# MainBorad.net
KiCad netlist of a schematic drawn in Altium Designer
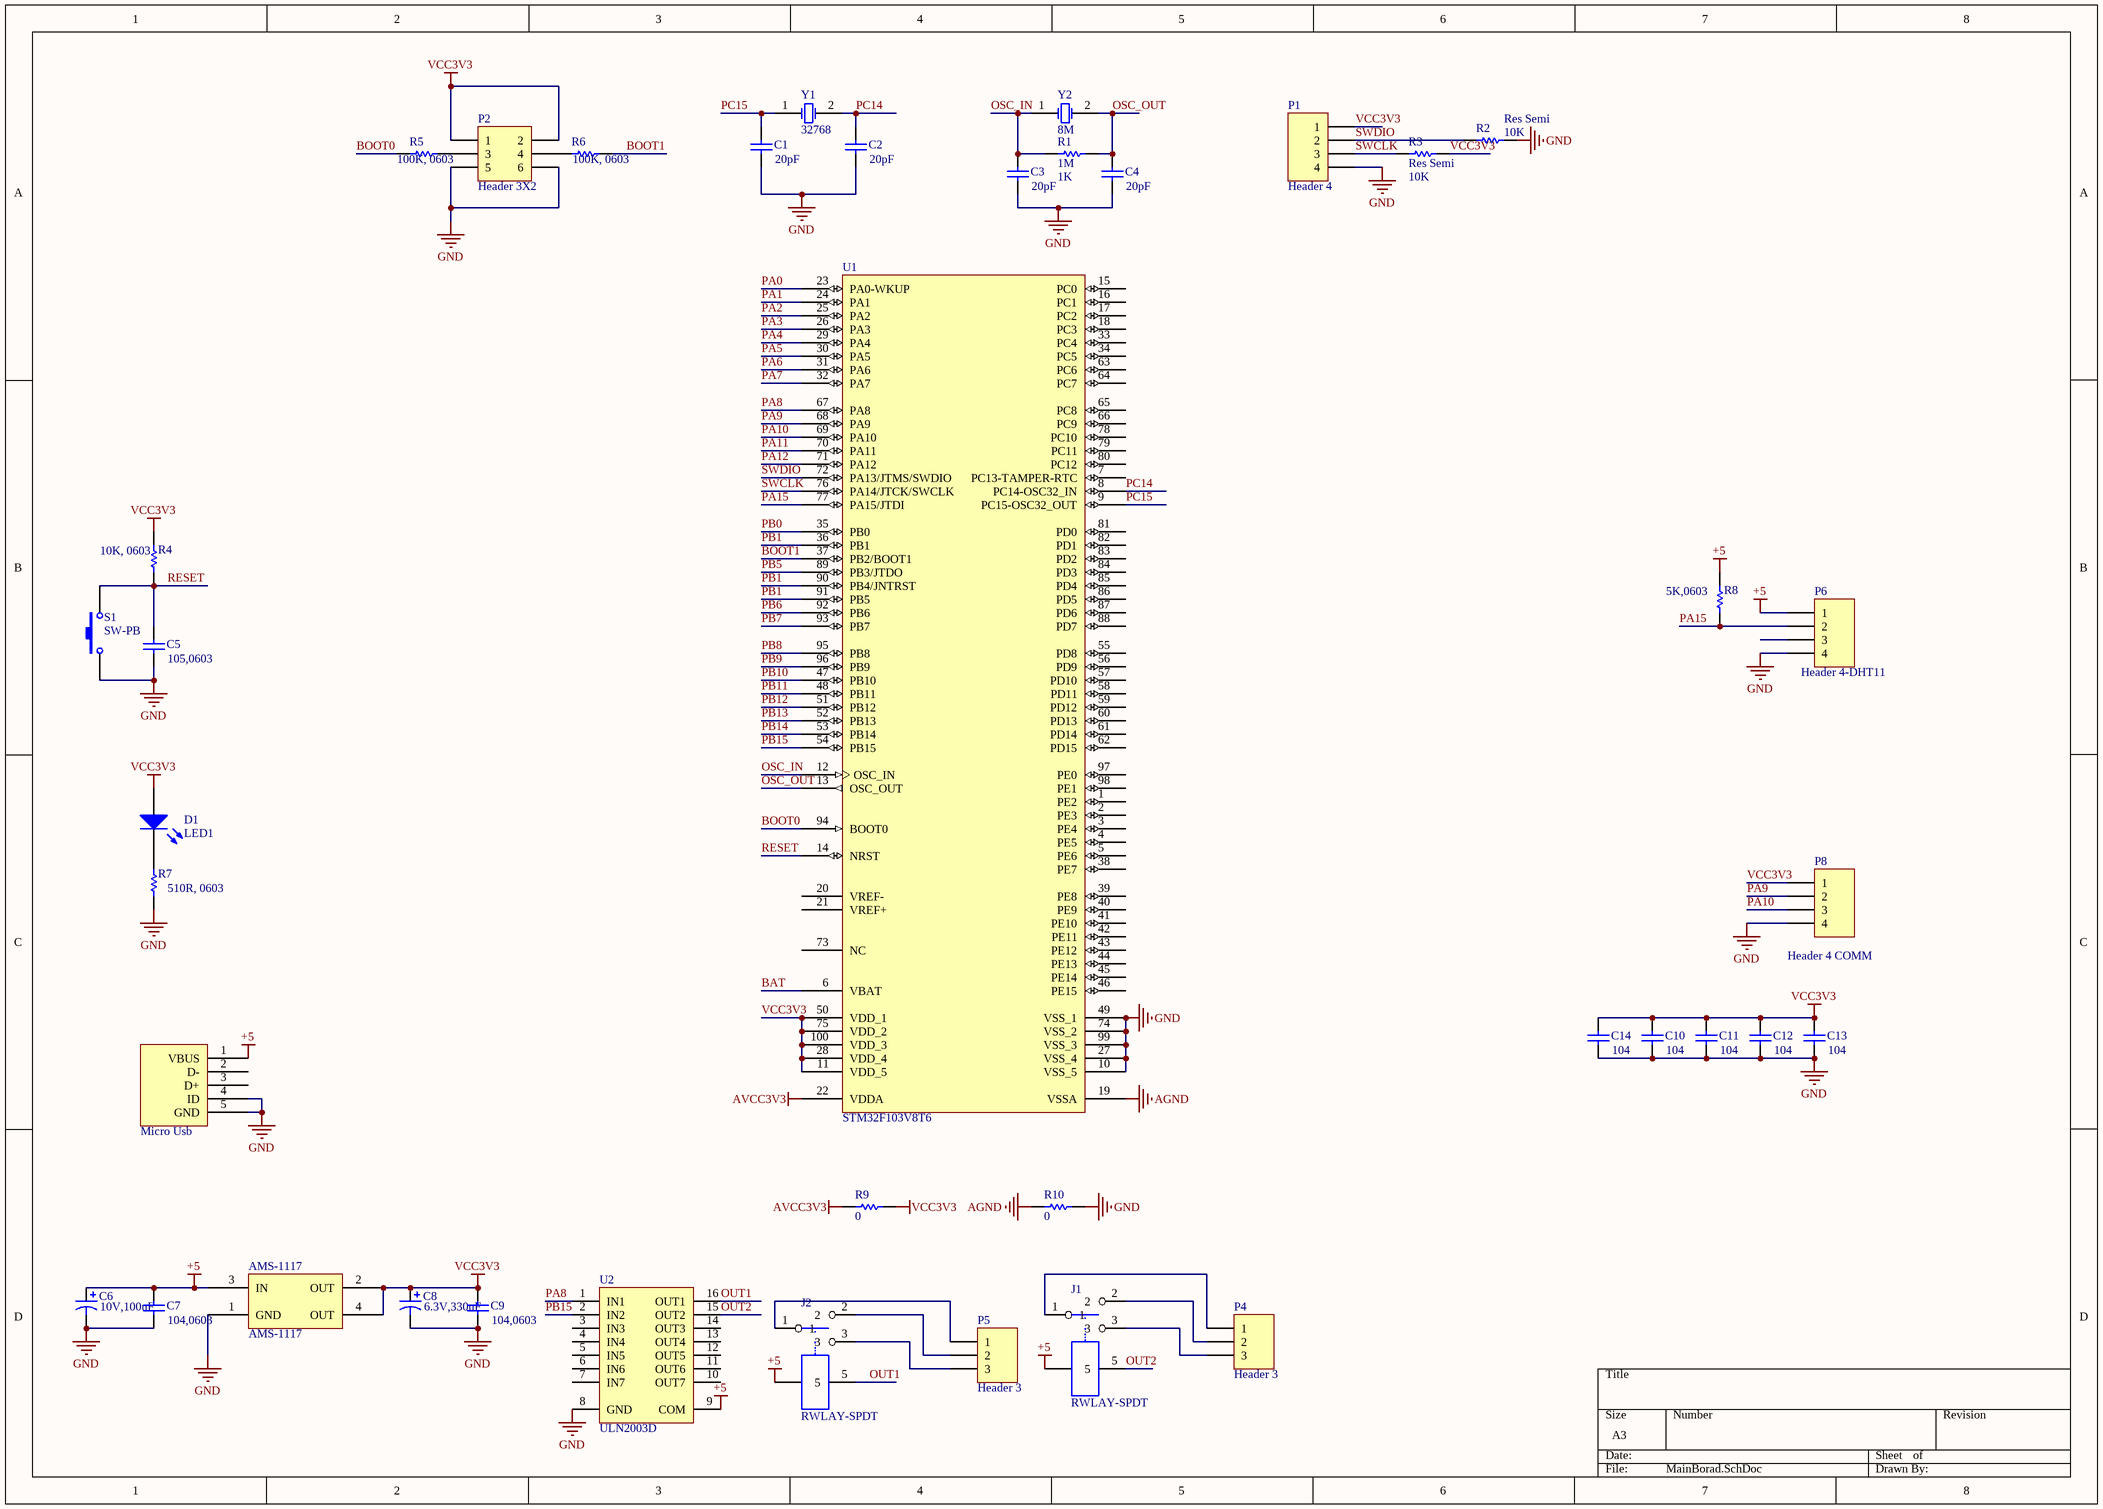
[diagram p0: MainBorad.SchDoc]

(export (version "E")
  (design (tool "Eeschema 10.0.6"))
  (components
    (comp (ref "AMS-1117")
      (value "AMS-1117")
      (footprint "SOT223")
      (libsource (lib "ams1117") (part "AMS-1117"))
    )
    (comp (ref "C1")
      (value "20pF")
      (footprint "0805C")
      (description "Capacitor (Semiconductor SIM Model)")
      (fields (field (name "Comment") "Cap Semi") (field (name "PUBLISHER") "Altium Limited"))
      (libsource (lib "Miscellaneous Devices") (part "Cap Semi"))
    )
    (comp (ref "C2")
      (value "20pF")
      (footprint "0805C")
      (description "Capacitor (Semiconductor SIM Model)")
      (fields (field (name "Comment") "Cap Semi") (field (name "PUBLISHER") "Altium Limited"))
      (libsource (lib "Miscellaneous Devices") (part "Cap Semi"))
    )
    (comp (ref "C3")
      (value "20pF")
      (footprint "0805C")
      (description "Capacitor (Semiconductor SIM Model)")
      (fields (field (name "Comment") "Cap Semi") (field (name "PUBLISHER") "Altium Limited"))
      (libsource (lib "Miscellaneous Devices") (part "Cap Semi"))
    )
    (comp (ref "C4")
      (value "20pF")
      (footprint "0805C")
      (description "Capacitor (Semiconductor SIM Model)")
      (fields (field (name "Comment") "Cap Semi") (field (name "PUBLISHER") "Altium Limited"))
      (libsource (lib "Miscellaneous Devices") (part "Cap Semi"))
    )
    (comp (ref "C5")
      (value "105,0603")
      (footprint "0805C")
      (description "Capacitor (Semiconductor SIM Model)")
      (fields (field (name "Comment") "Cap Semi") (field (name "PUBLISHER") "Altium Limited"))
      (libsource (lib "Miscellaneous Devices") (part "Cap Semi"))
    )
    (comp (ref "C6")
      (value "10V,100uF")
      (footprint "7343C")
      (description "Polarized Capacitor (Surface Mount)")
      (fields (field (name "Comment") "Cap Pol3") (field (name "PUBLISHER") "Altium Limited"))
      (libsource (lib "Miscellaneous Devices") (part "Cap Pol3"))
    )
    (comp (ref "C7")
      (value "104,0603")
      (footprint "0805C")
      (description "Capacitor (Semiconductor SIM Model)")
      (fields (field (name "Comment") "Cap Semi") (field (name "PUBLISHER") "Altium Limited"))
      (libsource (lib "Miscellaneous Devices") (part "Cap Semi"))
    )
    (comp (ref "C8")
      (value "6.3V,330uF")
      (footprint "7343C")
      (description "Polarized Capacitor (Surface Mount)")
      (fields (field (name "PUBLISHER") "Altium Limited"))
      (libsource (lib "Miscellaneous Devices") (part "Cap Pol3"))
    )
    (comp (ref "C9")
      (value "104,0603")
      (footprint "0805C")
      (description "Capacitor (Semiconductor SIM Model)")
      (fields (field (name "Comment") "Cap Semi") (field (name "PUBLISHER") "Altium Limited"))
      (libsource (lib "Miscellaneous Devices") (part "Cap Semi"))
    )
    (comp (ref "C10")
      (value "104")
      (footprint "0805C")
      (description "Capacitor (Semiconductor SIM Model)")
      (fields (field (name "Comment") "Cap Semi") (field (name "PUBLISHER") "Altium Limited"))
      (libsource (lib "Miscellaneous Devices") (part "Cap Semi"))
    )
    (comp (ref "C11")
      (value "104")
      (footprint "0805C")
      (description "Capacitor (Semiconductor SIM Model)")
      (fields (field (name "Comment") "Cap Semi") (field (name "PUBLISHER") "Altium Limited"))
      (libsource (lib "Miscellaneous Devices") (part "Cap Semi"))
    )
    (comp (ref "C12")
      (value "104")
      (footprint "0805C")
      (description "Capacitor (Semiconductor SIM Model)")
      (fields (field (name "Comment") "Cap Semi") (field (name "PUBLISHER") "Altium Limited"))
      (libsource (lib "Miscellaneous Devices") (part "Cap Semi"))
    )
    (comp (ref "C13")
      (value "104")
      (footprint "0805C")
      (description "Capacitor (Semiconductor SIM Model)")
      (fields (field (name "Comment") "Cap Semi") (field (name "PUBLISHER") "Altium Limited"))
      (libsource (lib "Miscellaneous Devices") (part "Cap Semi"))
    )
    (comp (ref "C14")
      (value "104")
      (footprint "0805C")
      (description "Capacitor (Semiconductor SIM Model)")
      (fields (field (name "Comment") "Cap Semi") (field (name "PUBLISHER") "Altium Limited"))
      (libsource (lib "Miscellaneous Devices") (part "Cap Semi"))
    )
    (comp (ref "D1")
      (value "LED1")
      (footprint "0805")
      (description "Typical RED GaAs LED")
      (fields (field (name "PUBLISHER") "Altium Limited"))
      (libsource (lib "Miscellaneous Devices") (part "LED1"))
    )
    (comp (ref "J1") (value "RWLAY-SPDT") (footprint "relay") (libsource (lib "J继电器") (part "RWLAY-SPDT")))
    (comp (ref "J2") (value "RWLAY-SPDT") (footprint "relay") (libsource (lib "J继电器") (part "RWLAY-SPDT")))
    (comp (ref "Micro Usb")
      (value "Micro Usb")
      (footprint "Micro_USB")
      (libsource (lib "micro_usb") (part "Micro Usb"))
    )
    (comp (ref "P1")
      (value "Header 4")
      (footprint "HDR1X4")
      (description "Header, 4-Pin")
      (fields (field (name "PUBLISHER") "Altium Limited"))
      (libsource (lib "Miscellaneous Connectors") (part "Header 4"))
    )
    (comp (ref "P2")
      (value "Header 3X2")
      (footprint "HDR2X3")
      (description "Header, 3-Pin, Dual row")
      (fields (field (name "PUBLISHER") "Altium Limited"))
      (libsource (lib "Miscellaneous Connectors") (part "Header 3X2"))
    )
    (comp (ref "P4")
      (value "Header 3")
      (footprint "HDR1X3")
      (description "Header, 3-Pin")
      (fields (field (name "PUBLISHER") "Altium Limited"))
      (libsource (lib "Miscellaneous Connectors") (part "Header 3"))
    )
    (comp (ref "P5")
      (value "Header 3")
      (footprint "HDR1X3")
      (description "Header, 3-Pin")
      (fields (field (name "PUBLISHER") "Altium Limited"))
      (libsource (lib "Miscellaneous Connectors") (part "Header 3"))
    )
    (comp (ref "P6")
      (value "Header 4-DHT11")
      (footprint "HDR1X4")
      (description "Header, 4-Pin")
      (fields (field (name "PUBLISHER") "Altium Limited"))
      (libsource (lib "") (part "Header 4_1"))
    )
    (comp (ref "P8")
      (value "Header 4 COMM")
      (footprint "HDR1X4")
      (description "Header, 4-Pin")
      (fields (field (name "PUBLISHER") "Altium Limited"))
      (libsource (lib "") (part "Header 4_1"))
    )
    (comp (ref "R1")
      (value "1M")
      (footprint "0805R")
      (description "Semiconductor Resistor")
      (fields (field (name "ALTIUM_VALUE") "1K") (field (name "PUBLISHER") "Altium Limited"))
      (libsource (lib "Miscellaneous Devices") (part "Res Semi"))
    )
    (comp (ref "R2")
      (value "Res Semi")
      (footprint "0805R")
      (description "Semiconductor Resistor")
      (fields (field (name "ALTIUM_VALUE") "10K") (field (name "PUBLISHER") "Altium Limited"))
      (libsource (lib "Miscellaneous Devices") (part "Res Semi"))
    )
    (comp (ref "R3")
      (value "Res Semi")
      (footprint "0805R")
      (description "Semiconductor Resistor")
      (fields (field (name "ALTIUM_VALUE") "10K") (field (name "PUBLISHER") "Altium Limited"))
      (libsource (lib "Miscellaneous Devices") (part "Res Semi"))
    )
    (comp (ref "R4")
      (value "10K, 0603")
      (footprint "0805R")
      (description "Semiconductor Resistor")
      (fields (field (name "Comment") "Res Semi") (field (name "PUBLISHER") "Altium Limited"))
      (libsource (lib "Miscellaneous Devices") (part "Res Semi"))
    )
    (comp (ref "R5")
      (value "100K, 0603")
      (footprint "0805R")
      (description "Semiconductor Resistor")
      (fields (field (name "Comment") "Res Semi") (field (name "PUBLISHER") "Altium Limited"))
      (libsource (lib "Miscellaneous Devices") (part "Res Semi"))
    )
    (comp (ref "R6")
      (value "100K, 0603")
      (footprint "0805R")
      (description "Semiconductor Resistor")
      (fields (field (name "Comment") "Res Semi") (field (name "PUBLISHER") "Altium Limited"))
      (libsource (lib "Miscellaneous Devices") (part "Res Semi"))
    )
    (comp (ref "R7")
      (value "510R, 0603")
      (footprint "0805R")
      (description "Semiconductor Resistor")
      (fields (field (name "Comment") "Res Semi") (field (name "PUBLISHER") "Altium Limited"))
      (libsource (lib "Miscellaneous Devices") (part "Res Semi"))
    )
    (comp (ref "R8")
      (value "5K,0603")
      (footprint "0805R")
      (description "Semiconductor Resistor")
      (fields (field (name "Comment") "Res Semi") (field (name "PUBLISHER") "Altium Limited"))
      (libsource (lib "Miscellaneous Devices") (part "Res Semi"))
    )
    (comp (ref "R9")
      (value "0")
      (footprint "0805R")
      (description "Semiconductor Resistor")
      (fields (field (name "Comment") "Res Semi") (field (name "PUBLISHER") "Altium Limited"))
      (libsource (lib "Miscellaneous Devices") (part "Res Semi"))
    )
    (comp (ref "R10")
      (value "0")
      (footprint "0805R")
      (description "Semiconductor Resistor")
      (fields (field (name "Comment") "Res Semi") (field (name "PUBLISHER") "Altium Limited"))
      (libsource (lib "Miscellaneous Devices") (part "Res Semi"))
    )
    (comp (ref "S1")
      (value "SW-PB")
      (footprint "SPST-2")
      (description "Switch")
      (fields (field (name "PUBLISHER") "Altium Limited"))
      (libsource (lib "Miscellaneous Devices") (part "SW-PB"))
    )
    (comp (ref "U1")
      (value "STM32F103V8T6")
      (footprint "LQFP100_N")
      (description "STM32 ARM-based 32-bit MCU with 64 Kbytes Flash, 100-pin LQFP, Industrial Temperature")
      (fields (field (name "PUBLISHER") "*"))
      (libsource (lib "ST Microcontroller 32-Bit STM32 SCH") (part "STM32F103V8T6"))
    )
    (comp (ref "U2")
      (value "ULN2003D")
      (footprint "SO16_N")
      (description "Seven Darlington Array")
      (fields (field (name "PUBLISHER") "Altium Limited"))
      (libsource (lib "ST Interface Darlington Driver") (part "ULN2003D"))
    )
    (comp (ref "Y1")
      (value "32768")
      (footprint "R38")
      (description "Crystal Oscillator")
      (fields (field (name "PUBLISHER") "Altium Limited"))
      (libsource (lib "Miscellaneous Devices") (part "XTAL"))
    )
    (comp (ref "Y2")
      (value "8M")
      (footprint "XTAL1")
      (description "Crystal Oscillator")
      (fields (field (name "PUBLISHER") "Altium Limited"))
      (libsource (lib "Miscellaneous Devices") (part "XTAL"))
    )
  )
  (nets
    (net (code "1") (name "+5") (class "Default")
      (node (ref "AMS-1117") (pin "3") (pinfunction "IN_3") (pintype "passive"))
      (node (ref "C6") (pin "1") (pinfunction "1_1") (pintype "passive"))
      (node (ref "C7") (pin "2") (pinfunction "2_2") (pintype "passive"))
      (node (ref "J1") (pin "4") (pinfunction "4_4") (pintype "passive"))
      (node (ref "J2") (pin "4") (pinfunction "4_4") (pintype "passive"))
      (node (ref "Micro Usb") (pin "1") (pinfunction "VBUS_1") (pintype "passive"))
      (node (ref "P6") (pin "1") (pinfunction "1_1") (pintype "passive"))
      (node (ref "R8") (pin "2") (pinfunction "2_2") (pintype "passive"))
      (node (ref "U2") (pin "9") (pinfunction "COM_9") (pintype "passive"))
    )
    (net (code "2") (name "/BAT") (class "Default")
      (node (ref "U1") (pin "6") (pinfunction "VBAT_6") (pintype "power_in"))
    )
    (net (code "3") (name "/BOOT0") (class "Default")
      (node (ref "R5") (pin "2") (pinfunction "2_2") (pintype "passive"))
      (node (ref "U1") (pin "94") (pinfunction "BOOT0_94") (pintype "input"))
    )
    (net (code "4") (name "/BOOT1") (class "Default")
      (node (ref "R6") (pin "1") (pinfunction "1_1") (pintype "passive"))
      (node (ref "U1") (pin "37") (pinfunction "PB2/BOOT1_37") (pintype "bidirectional"))
    )
    (net (code "5") (name "/OSC_IN") (class "Default")
      (node (ref "C3") (pin "2") (pinfunction "2_2") (pintype "passive"))
      (node (ref "R1") (pin "1") (pinfunction "1_1") (pintype "passive"))
      (node (ref "U1") (pin "12") (pinfunction "OSC_IN_12") (pintype "input"))
      (node (ref "Y2") (pin "1") (pinfunction "OSC1_1") (pintype "passive"))
    )
    (net (code "6") (name "/OSC_OUT") (class "Default")
      (node (ref "C4") (pin "2") (pinfunction "2_2") (pintype "passive"))
      (node (ref "R1") (pin "2") (pinfunction "2_2") (pintype "passive"))
      (node (ref "U1") (pin "13") (pinfunction "OSC_OUT_13") (pintype "output"))
      (node (ref "Y2") (pin "2") (pinfunction "OSC2_2") (pintype "passive"))
    )
    (net (code "7") (name "/OUT1") (class "Default")
      (node (ref "J2") (pin "5") (pinfunction "5_5") (pintype "passive"))
      (node (ref "U2") (pin "16") (pinfunction "OUT1_16") (pintype "open_collector"))
    )
    (net (code "8") (name "/OUT2") (class "Default")
      (node (ref "J1") (pin "5") (pinfunction "5_5") (pintype "passive"))
      (node (ref "U2") (pin "15") (pinfunction "OUT2_15") (pintype "open_collector"))
    )
    (net (code "9") (name "/PA0") (class "Default")
      (node (ref "U1") (pin "23") (pinfunction "PA0-WKUP_23") (pintype "bidirectional"))
    )
    (net (code "10") (name "/PA1") (class "Default")
      (node (ref "U1") (pin "24") (pinfunction "PA1_24") (pintype "bidirectional"))
    )
    (net (code "11") (name "/PA2") (class "Default")
      (node (ref "U1") (pin "25") (pinfunction "PA2_25") (pintype "bidirectional"))
    )
    (net (code "12") (name "/PA3") (class "Default")
      (node (ref "U1") (pin "26") (pinfunction "PA3_26") (pintype "bidirectional"))
    )
    (net (code "13") (name "/PA4") (class "Default")
      (node (ref "U1") (pin "29") (pinfunction "PA4_29") (pintype "bidirectional"))
    )
    (net (code "14") (name "/PA5") (class "Default")
      (node (ref "U1") (pin "30") (pinfunction "PA5_30") (pintype "bidirectional"))
    )
    (net (code "15") (name "/PA6") (class "Default")
      (node (ref "U1") (pin "31") (pinfunction "PA6_31") (pintype "bidirectional"))
    )
    (net (code "16") (name "/PA7") (class "Default")
      (node (ref "U1") (pin "32") (pinfunction "PA7_32") (pintype "bidirectional"))
    )
    (net (code "17") (name "/PA8") (class "Default")
      (node (ref "U1") (pin "67") (pinfunction "PA8_67") (pintype "bidirectional"))
      (node (ref "U2") (pin "1") (pinfunction "IN1_1") (pintype "passive"))
    )
    (net (code "18") (name "/PA9") (class "Default")
      (node (ref "P8") (pin "2") (pinfunction "2_2") (pintype "passive"))
      (node (ref "U1") (pin "68") (pinfunction "PA9_68") (pintype "bidirectional"))
    )
    (net (code "19") (name "/PA10") (class "Default")
      (node (ref "P8") (pin "3") (pinfunction "3_3") (pintype "passive"))
      (node (ref "U1") (pin "69") (pinfunction "PA10_69") (pintype "bidirectional"))
    )
    (net (code "20") (name "/PA11") (class "Default")
      (node (ref "U1") (pin "70") (pinfunction "PA11_70") (pintype "bidirectional"))
    )
    (net (code "21") (name "/PA12") (class "Default")
      (node (ref "U1") (pin "71") (pinfunction "PA12_71") (pintype "bidirectional"))
    )
    (net (code "22") (name "/PA15") (class "Default")
      (node (ref "P6") (pin "2") (pinfunction "2_2") (pintype "passive"))
      (node (ref "R8") (pin "1") (pinfunction "1_1") (pintype "passive"))
      (node (ref "U1") (pin "77") (pinfunction "PA15/JTDI_77") (pintype "bidirectional"))
    )
    (net (code "23") (name "/PB0") (class "Default")
      (node (ref "U1") (pin "35") (pinfunction "PB0_35") (pintype "bidirectional"))
    )
    (net (code "24") (name "/PB1") (class "Default")
      (node (ref "U1") (pin "36") (pinfunction "PB1_36") (pintype "bidirectional"))
      (node (ref "U1") (pin "90") (pinfunction "PB4/JNTRST_90") (pintype "bidirectional"))
      (node (ref "U1") (pin "91") (pinfunction "PB5_91") (pintype "bidirectional"))
    )
    (net (code "25") (name "/PB5") (class "Default")
      (node (ref "U1") (pin "89") (pinfunction "PB3/JTDO_89") (pintype "bidirectional"))
    )
    (net (code "26") (name "/PB6") (class "Default")
      (node (ref "U1") (pin "92") (pinfunction "PB6_92") (pintype "bidirectional"))
    )
    (net (code "27") (name "/PB7") (class "Default")
      (node (ref "U1") (pin "93") (pinfunction "PB7_93") (pintype "bidirectional"))
    )
    (net (code "28") (name "/PB8") (class "Default")
      (node (ref "U1") (pin "95") (pinfunction "PB8_95") (pintype "bidirectional"))
    )
    (net (code "29") (name "/PB9") (class "Default")
      (node (ref "U1") (pin "96") (pinfunction "PB9_96") (pintype "bidirectional"))
    )
    (net (code "30") (name "/PB10") (class "Default")
      (node (ref "U1") (pin "47") (pinfunction "PB10_47") (pintype "bidirectional"))
    )
    (net (code "31") (name "/PB11") (class "Default")
      (node (ref "U1") (pin "48") (pinfunction "PB11_48") (pintype "bidirectional"))
    )
    (net (code "32") (name "/PB12") (class "Default")
      (node (ref "U1") (pin "51") (pinfunction "PB12_51") (pintype "bidirectional"))
    )
    (net (code "33") (name "/PB13") (class "Default")
      (node (ref "U1") (pin "52") (pinfunction "PB13_52") (pintype "bidirectional"))
    )
    (net (code "34") (name "/PB14") (class "Default")
      (node (ref "U1") (pin "53") (pinfunction "PB14_53") (pintype "bidirectional"))
    )
    (net (code "35") (name "/PB15") (class "Default")
      (node (ref "U1") (pin "54") (pinfunction "PB15_54") (pintype "bidirectional"))
      (node (ref "U2") (pin "2") (pinfunction "IN2_2") (pintype "passive"))
    )
    (net (code "36") (name "/PC14") (class "Default")
      (node (ref "C2") (pin "2") (pinfunction "2_2") (pintype "passive"))
      (node (ref "U1") (pin "8") (pinfunction "PC14-OSC32_IN_8") (pintype "bidirectional"))
      (node (ref "Y1") (pin "2") (pinfunction "OSC2_2") (pintype "passive"))
    )
    (net (code "37") (name "/PC15") (class "Default")
      (node (ref "C1") (pin "2") (pinfunction "2_2") (pintype "passive"))
      (node (ref "U1") (pin "9") (pinfunction "PC15-OSC32_OUT_9") (pintype "bidirectional"))
      (node (ref "Y1") (pin "1") (pinfunction "OSC1_1") (pintype "passive"))
    )
    (net (code "38") (name "/RESET") (class "Default")
      (node (ref "C5") (pin "2") (pinfunction "2_2") (pintype "passive"))
      (node (ref "R4") (pin "1") (pinfunction "1_1") (pintype "passive"))
      (node (ref "S1") (pin "2") (pinfunction "2_2") (pintype "passive"))
      (node (ref "U1") (pin "14") (pinfunction "NRST_14") (pintype "bidirectional"))
    )
    (net (code "39") (name "/SWCLK") (class "Default")
      (node (ref "P1") (pin "3") (pinfunction "3_3") (pintype "passive"))
      (node (ref "R3") (pin "2") (pinfunction "2_2") (pintype "passive"))
      (node (ref "U1") (pin "76") (pinfunction "PA14/JTCK/SWCLK_76") (pintype "bidirectional"))
    )
    (net (code "40") (name "/SWDIO") (class "Default")
      (node (ref "P1") (pin "2") (pinfunction "2_2") (pintype "passive"))
      (node (ref "R2") (pin "2") (pinfunction "2_2") (pintype "passive"))
      (node (ref "U1") (pin "72") (pinfunction "PA13/JTMS/SWDIO_72") (pintype "bidirectional"))
    )
    (net (code "41") (name "AGND") (class "Default")
      (node (ref "R10") (pin "2") (pinfunction "2_2") (pintype "passive"))
      (node (ref "U1") (pin "19") (pinfunction "VSSA_19") (pintype "power_in"))
    )
    (net (code "42") (name "AVCC3V3") (class "Default")
      (node (ref "R9") (pin "2") (pinfunction "2_2") (pintype "passive"))
      (node (ref "U1") (pin "22") (pinfunction "VDDA_22") (pintype "power_in"))
    )
    (net (code "43") (name "GND") (class "Default")
      (node (ref "AMS-1117") (pin "1") (pinfunction "GND_1") (pintype "power_in"))
      (node (ref "C1") (pin "1") (pinfunction "1_1") (pintype "passive"))
      (node (ref "C10") (pin "1") (pinfunction "1_1") (pintype "passive"))
      (node (ref "C11") (pin "1") (pinfunction "1_1") (pintype "passive"))
      (node (ref "C12") (pin "1") (pinfunction "1_1") (pintype "passive"))
      (node (ref "C13") (pin "1") (pinfunction "1_1") (pintype "passive"))
      (node (ref "C14") (pin "1") (pinfunction "1_1") (pintype "passive"))
      (node (ref "C2") (pin "1") (pinfunction "1_1") (pintype "passive"))
      (node (ref "C3") (pin "1") (pinfunction "1_1") (pintype "passive"))
      (node (ref "C4") (pin "1") (pinfunction "1_1") (pintype "passive"))
      (node (ref "C5") (pin "1") (pinfunction "1_1") (pintype "passive"))
      (node (ref "C6") (pin "2") (pinfunction "2_2") (pintype "passive"))
      (node (ref "C7") (pin "1") (pinfunction "1_1") (pintype "passive"))
      (node (ref "C8") (pin "2") (pinfunction "2_2") (pintype "passive"))
      (node (ref "C9") (pin "1") (pinfunction "1_1") (pintype "passive"))
      (node (ref "Micro Usb") (pin "4") (pinfunction "ID_4") (pintype "passive"))
      (node (ref "Micro Usb") (pin "5") (pinfunction "GND_5") (pintype "passive"))
      (node (ref "P1") (pin "4") (pinfunction "4_4") (pintype "passive"))
      (node (ref "P2") (pin "5") (pinfunction "5_5") (pintype "passive"))
      (node (ref "P2") (pin "6") (pinfunction "6_6") (pintype "passive"))
      (node (ref "P6") (pin "4") (pinfunction "4_4") (pintype "passive"))
      (node (ref "P8") (pin "4") (pinfunction "4_4") (pintype "passive"))
      (node (ref "R10") (pin "1") (pinfunction "1_1") (pintype "passive"))
      (node (ref "R2") (pin "1") (pinfunction "1_1") (pintype "passive"))
      (node (ref "R7") (pin "1") (pinfunction "1_1") (pintype "passive"))
      (node (ref "S1") (pin "1") (pinfunction "1_1") (pintype "passive"))
      (node (ref "U1") (pin "10") (pinfunction "VSS_5_10") (pintype "power_in"))
      (node (ref "U1") (pin "27") (pinfunction "VSS_4_27") (pintype "power_in"))
      (node (ref "U1") (pin "49") (pinfunction "VSS_1_49") (pintype "power_in"))
      (node (ref "U1") (pin "74") (pinfunction "VSS_2_74") (pintype "power_in"))
      (node (ref "U1") (pin "99") (pinfunction "VSS_3_99") (pintype "power_in"))
      (node (ref "U2") (pin "8") (pinfunction "GND_8") (pintype "power_in"))
    )
    (net (code "44") (name "Net-(D1-K)") (class "Default")
      (node (ref "D1") (pin "2") (pinfunction "K_2") (pintype "passive"))
      (node (ref "R7") (pin "2") (pinfunction "2_2") (pintype "passive"))
    )
    (net (code "45") (name "Net-(J1-Pad1)") (class "Default")
      (node (ref "J1") (pin "1") (pinfunction "1_1") (pintype "passive"))
      (node (ref "P4") (pin "1") (pinfunction "1_1") (pintype "passive"))
    )
    (net (code "46") (name "Net-(J1-Pad2)") (class "Default")
      (node (ref "J1") (pin "2") (pinfunction "2_2") (pintype "passive"))
      (node (ref "P4") (pin "2") (pinfunction "2_2") (pintype "passive"))
    )
    (net (code "47") (name "Net-(J1-Pad3)") (class "Default")
      (node (ref "J1") (pin "3") (pinfunction "3_3") (pintype "passive"))
      (node (ref "P4") (pin "3") (pinfunction "3_3") (pintype "passive"))
    )
    (net (code "48") (name "Net-(J2-Pad1)") (class "Default")
      (node (ref "J2") (pin "1") (pinfunction "1_1") (pintype "passive"))
      (node (ref "P5") (pin "1") (pinfunction "1_1") (pintype "passive"))
    )
    (net (code "49") (name "Net-(J2-Pad2)") (class "Default")
      (node (ref "J2") (pin "2") (pinfunction "2_2") (pintype "passive"))
      (node (ref "P5") (pin "2") (pinfunction "2_2") (pintype "passive"))
    )
    (net (code "50") (name "Net-(J2-Pad3)") (class "Default")
      (node (ref "J2") (pin "3") (pinfunction "3_3") (pintype "passive"))
      (node (ref "P5") (pin "3") (pinfunction "3_3") (pintype "passive"))
    )
    (net (code "51") (name "Net-(P2-Pad3)") (class "Default")
      (node (ref "P2") (pin "3") (pinfunction "3_3") (pintype "passive"))
      (node (ref "R5") (pin "1") (pinfunction "1_1") (pintype "passive"))
    )
    (net (code "52") (name "Net-(P2-Pad4)") (class "Default")
      (node (ref "P2") (pin "4") (pinfunction "4_4") (pintype "passive"))
      (node (ref "R6") (pin "2") (pinfunction "2_2") (pintype "passive"))
    )
    (net (code "53") (name "VCC3V3") (class "Default")
      (node (ref "AMS-1117") (pin "2") (pinfunction "OUT_2") (pintype "passive"))
      (node (ref "AMS-1117") (pin "4") (pinfunction "OUT_4") (pintype "passive"))
      (node (ref "C10") (pin "2") (pinfunction "2_2") (pintype "passive"))
      (node (ref "C11") (pin "2") (pinfunction "2_2") (pintype "passive"))
      (node (ref "C12") (pin "2") (pinfunction "2_2") (pintype "passive"))
      (node (ref "C13") (pin "2") (pinfunction "2_2") (pintype "passive"))
      (node (ref "C14") (pin "2") (pinfunction "2_2") (pintype "passive"))
      (node (ref "C8") (pin "1") (pinfunction "1_1") (pintype "passive"))
      (node (ref "C9") (pin "2") (pinfunction "2_2") (pintype "passive"))
      (node (ref "D1") (pin "1") (pinfunction "A_1") (pintype "passive"))
      (node (ref "P1") (pin "1") (pinfunction "1_1") (pintype "passive"))
      (node (ref "P2") (pin "1") (pinfunction "1_1") (pintype "passive"))
      (node (ref "P2") (pin "2") (pinfunction "2_2") (pintype "passive"))
      (node (ref "P8") (pin "1") (pinfunction "1_1") (pintype "passive"))
      (node (ref "R3") (pin "1") (pinfunction "1_1") (pintype "passive"))
      (node (ref "R4") (pin "2") (pinfunction "2_2") (pintype "passive"))
      (node (ref "R9") (pin "1") (pinfunction "1_1") (pintype "passive"))
      (node (ref "U1") (pin "100") (pinfunction "VDD_3_100") (pintype "power_in"))
      (node (ref "U1") (pin "11") (pinfunction "VDD_5_11") (pintype "power_in"))
      (node (ref "U1") (pin "28") (pinfunction "VDD_4_28") (pintype "power_in"))
      (node (ref "U1") (pin "50") (pinfunction "VDD_1_50") (pintype "power_in"))
      (node (ref "U1") (pin "75") (pinfunction "VDD_2_75") (pintype "power_in"))
    )
    (net (code "54") (name "unconnected-(Micro Usb-D+-Pad3)") (class "Default")
      (node (ref "Micro Usb") (pin "3") (pinfunction "D+_3") (pintype "passive"))
    )
    (net (code "55") (name "unconnected-(Micro Usb-D--Pad2)") (class "Default")
      (node (ref "Micro Usb") (pin "2") (pinfunction "D-_2") (pintype "passive"))
    )
    (net (code "56") (name "unconnected-(P6-Pad3)") (class "Default")
      (node (ref "P6") (pin "3") (pinfunction "3_3") (pintype "passive"))
    )
    (net (code "57") (name "unconnected-(U1-NC-Pad73)") (class "Default")
      (node (ref "U1") (pin "73") (pinfunction "NC_73") (pintype "passive"))
    )
    (net (code "58") (name "unconnected-(U1-PC0-Pad15)") (class "Default")
      (node (ref "U1") (pin "15") (pinfunction "PC0_15") (pintype "bidirectional"))
    )
    (net (code "59") (name "unconnected-(U1-PC1-Pad16)") (class "Default")
      (node (ref "U1") (pin "16") (pinfunction "PC1_16") (pintype "bidirectional"))
    )
    (net (code "60") (name "unconnected-(U1-PC2-Pad17)") (class "Default")
      (node (ref "U1") (pin "17") (pinfunction "PC2_17") (pintype "bidirectional"))
    )
    (net (code "61") (name "unconnected-(U1-PC3-Pad18)") (class "Default")
      (node (ref "U1") (pin "18") (pinfunction "PC3_18") (pintype "bidirectional"))
    )
    (net (code "62") (name "unconnected-(U1-PC4-Pad33)") (class "Default")
      (node (ref "U1") (pin "33") (pinfunction "PC4_33") (pintype "bidirectional"))
    )
    (net (code "63") (name "unconnected-(U1-PC5-Pad34)") (class "Default")
      (node (ref "U1") (pin "34") (pinfunction "PC5_34") (pintype "bidirectional"))
    )
    (net (code "64") (name "unconnected-(U1-PC6-Pad63)") (class "Default")
      (node (ref "U1") (pin "63") (pinfunction "PC6_63") (pintype "bidirectional"))
    )
    (net (code "65") (name "unconnected-(U1-PC7-Pad64)") (class "Default")
      (node (ref "U1") (pin "64") (pinfunction "PC7_64") (pintype "bidirectional"))
    )
    (net (code "66") (name "unconnected-(U1-PC8-Pad65)") (class "Default")
      (node (ref "U1") (pin "65") (pinfunction "PC8_65") (pintype "bidirectional"))
    )
    (net (code "67") (name "unconnected-(U1-PC9-Pad66)") (class "Default")
      (node (ref "U1") (pin "66") (pinfunction "PC9_66") (pintype "bidirectional"))
    )
    (net (code "68") (name "unconnected-(U1-PC10-Pad78)") (class "Default")
      (node (ref "U1") (pin "78") (pinfunction "PC10_78") (pintype "bidirectional"))
    )
    (net (code "69") (name "unconnected-(U1-PC11-Pad79)") (class "Default")
      (node (ref "U1") (pin "79") (pinfunction "PC11_79") (pintype "bidirectional"))
    )
    (net (code "70") (name "unconnected-(U1-PC12-Pad80)") (class "Default")
      (node (ref "U1") (pin "80") (pinfunction "PC12_80") (pintype "bidirectional"))
    )
    (net (code "71") (name "unconnected-(U1-PC13-TAMPER-RTC-Pad7)") (class "Default")
      (node (ref "U1") (pin "7") (pinfunction "PC13-TAMPER-RTC_7") (pintype "bidirectional"))
    )
    (net (code "72") (name "unconnected-(U1-PD0-Pad81)") (class "Default")
      (node (ref "U1") (pin "81") (pinfunction "PD0_81") (pintype "bidirectional"))
    )
    (net (code "73") (name "unconnected-(U1-PD1-Pad82)") (class "Default")
      (node (ref "U1") (pin "82") (pinfunction "PD1_82") (pintype "bidirectional"))
    )
    (net (code "74") (name "unconnected-(U1-PD2-Pad83)") (class "Default")
      (node (ref "U1") (pin "83") (pinfunction "PD2_83") (pintype "bidirectional"))
    )
    (net (code "75") (name "unconnected-(U1-PD3-Pad84)") (class "Default")
      (node (ref "U1") (pin "84") (pinfunction "PD3_84") (pintype "bidirectional"))
    )
    (net (code "76") (name "unconnected-(U1-PD4-Pad85)") (class "Default")
      (node (ref "U1") (pin "85") (pinfunction "PD4_85") (pintype "bidirectional"))
    )
    (net (code "77") (name "unconnected-(U1-PD5-Pad86)") (class "Default")
      (node (ref "U1") (pin "86") (pinfunction "PD5_86") (pintype "bidirectional"))
    )
    (net (code "78") (name "unconnected-(U1-PD6-Pad87)") (class "Default")
      (node (ref "U1") (pin "87") (pinfunction "PD6_87") (pintype "bidirectional"))
    )
    (net (code "79") (name "unconnected-(U1-PD7-Pad88)") (class "Default")
      (node (ref "U1") (pin "88") (pinfunction "PD7_88") (pintype "bidirectional"))
    )
    (net (code "80") (name "unconnected-(U1-PD8-Pad55)") (class "Default")
      (node (ref "U1") (pin "55") (pinfunction "PD8_55") (pintype "bidirectional"))
    )
    (net (code "81") (name "unconnected-(U1-PD9-Pad56)") (class "Default")
      (node (ref "U1") (pin "56") (pinfunction "PD9_56") (pintype "bidirectional"))
    )
    (net (code "82") (name "unconnected-(U1-PD10-Pad57)") (class "Default")
      (node (ref "U1") (pin "57") (pinfunction "PD10_57") (pintype "bidirectional"))
    )
    (net (code "83") (name "unconnected-(U1-PD11-Pad58)") (class "Default")
      (node (ref "U1") (pin "58") (pinfunction "PD11_58") (pintype "bidirectional"))
    )
    (net (code "84") (name "unconnected-(U1-PD12-Pad59)") (class "Default")
      (node (ref "U1") (pin "59") (pinfunction "PD12_59") (pintype "bidirectional"))
    )
    (net (code "85") (name "unconnected-(U1-PD13-Pad60)") (class "Default")
      (node (ref "U1") (pin "60") (pinfunction "PD13_60") (pintype "bidirectional"))
    )
    (net (code "86") (name "unconnected-(U1-PD14-Pad61)") (class "Default")
      (node (ref "U1") (pin "61") (pinfunction "PD14_61") (pintype "bidirectional"))
    )
    (net (code "87") (name "unconnected-(U1-PD15-Pad62)") (class "Default")
      (node (ref "U1") (pin "62") (pinfunction "PD15_62") (pintype "bidirectional"))
    )
    (net (code "88") (name "unconnected-(U1-PE0-Pad97)") (class "Default")
      (node (ref "U1") (pin "97") (pinfunction "PE0_97") (pintype "bidirectional"))
    )
    (net (code "89") (name "unconnected-(U1-PE1-Pad98)") (class "Default")
      (node (ref "U1") (pin "98") (pinfunction "PE1_98") (pintype "bidirectional"))
    )
    (net (code "90") (name "unconnected-(U1-PE2-Pad1)") (class "Default")
      (node (ref "U1") (pin "1") (pinfunction "PE2_1") (pintype "bidirectional"))
    )
    (net (code "91") (name "unconnected-(U1-PE3-Pad2)") (class "Default")
      (node (ref "U1") (pin "2") (pinfunction "PE3_2") (pintype "bidirectional"))
    )
    (net (code "92") (name "unconnected-(U1-PE4-Pad3)") (class "Default")
      (node (ref "U1") (pin "3") (pinfunction "PE4_3") (pintype "bidirectional"))
    )
    (net (code "93") (name "unconnected-(U1-PE5-Pad4)") (class "Default")
      (node (ref "U1") (pin "4") (pinfunction "PE5_4") (pintype "bidirectional"))
    )
    (net (code "94") (name "unconnected-(U1-PE6-Pad5)") (class "Default")
      (node (ref "U1") (pin "5") (pinfunction "PE6_5") (pintype "bidirectional"))
    )
    (net (code "95") (name "unconnected-(U1-PE7-Pad38)") (class "Default")
      (node (ref "U1") (pin "38") (pinfunction "PE7_38") (pintype "bidirectional"))
    )
    (net (code "96") (name "unconnected-(U1-PE8-Pad39)") (class "Default")
      (node (ref "U1") (pin "39") (pinfunction "PE8_39") (pintype "bidirectional"))
    )
    (net (code "97") (name "unconnected-(U1-PE9-Pad40)") (class "Default")
      (node (ref "U1") (pin "40") (pinfunction "PE9_40") (pintype "bidirectional"))
    )
    (net (code "98") (name "unconnected-(U1-PE10-Pad41)") (class "Default")
      (node (ref "U1") (pin "41") (pinfunction "PE10_41") (pintype "bidirectional"))
    )
    (net (code "99") (name "unconnected-(U1-PE11-Pad42)") (class "Default")
      (node (ref "U1") (pin "42") (pinfunction "PE11_42") (pintype "bidirectional"))
    )
    (net (code "100") (name "unconnected-(U1-PE12-Pad43)") (class "Default")
      (node (ref "U1") (pin "43") (pinfunction "PE12_43") (pintype "bidirectional"))
    )
    (net (code "101") (name "unconnected-(U1-PE13-Pad44)") (class "Default")
      (node (ref "U1") (pin "44") (pinfunction "PE13_44") (pintype "bidirectional"))
    )
    (net (code "102") (name "unconnected-(U1-PE14-Pad45)") (class "Default")
      (node (ref "U1") (pin "45") (pinfunction "PE14_45") (pintype "bidirectional"))
    )
    (net (code "103") (name "unconnected-(U1-PE15-Pad46)") (class "Default")
      (node (ref "U1") (pin "46") (pinfunction "PE15_46") (pintype "bidirectional"))
    )
    (net (code "104") (name "unconnected-(U1-VREF+-Pad21)") (class "Default")
      (node (ref "U1") (pin "21") (pinfunction "VREF+_21") (pintype "power_in"))
    )
    (net (code "105") (name "unconnected-(U1-VREF--Pad20)") (class "Default")
      (node (ref "U1") (pin "20") (pinfunction "VREF-_20") (pintype "power_in"))
    )
    (net (code "106") (name "unconnected-(U2-IN3-Pad3)") (class "Default")
      (node (ref "U2") (pin "3") (pinfunction "IN3_3") (pintype "passive"))
    )
    (net (code "107") (name "unconnected-(U2-IN4-Pad4)") (class "Default")
      (node (ref "U2") (pin "4") (pinfunction "IN4_4") (pintype "passive"))
    )
    (net (code "108") (name "unconnected-(U2-IN5-Pad5)") (class "Default")
      (node (ref "U2") (pin "5") (pinfunction "IN5_5") (pintype "passive"))
    )
    (net (code "109") (name "unconnected-(U2-IN6-Pad6)") (class "Default")
      (node (ref "U2") (pin "6") (pinfunction "IN6_6") (pintype "passive"))
    )
    (net (code "110") (name "unconnected-(U2-IN7-Pad7)") (class "Default")
      (node (ref "U2") (pin "7") (pinfunction "IN7_7") (pintype "passive"))
    )
    (net (code "111") (name "unconnected-(U2-OUT3-Pad14)") (class "Default")
      (node (ref "U2") (pin "14") (pinfunction "OUT3_14") (pintype "open_collector"))
    )
    (net (code "112") (name "unconnected-(U2-OUT4-Pad13)") (class "Default")
      (node (ref "U2") (pin "13") (pinfunction "OUT4_13") (pintype "open_collector"))
    )
    (net (code "113") (name "unconnected-(U2-OUT5-Pad12)") (class "Default")
      (node (ref "U2") (pin "12") (pinfunction "OUT5_12") (pintype "open_collector"))
    )
    (net (code "114") (name "unconnected-(U2-OUT6-Pad11)") (class "Default")
      (node (ref "U2") (pin "11") (pinfunction "OUT6_11") (pintype "open_collector"))
    )
    (net (code "115") (name "unconnected-(U2-OUT7-Pad10)") (class "Default")
      (node (ref "U2") (pin "10") (pinfunction "OUT7_10") (pintype "open_collector"))
    )
  )
)
